# Project_Node_Sensors.net
KiCad netlist of a schematic drawn in Altium Designer
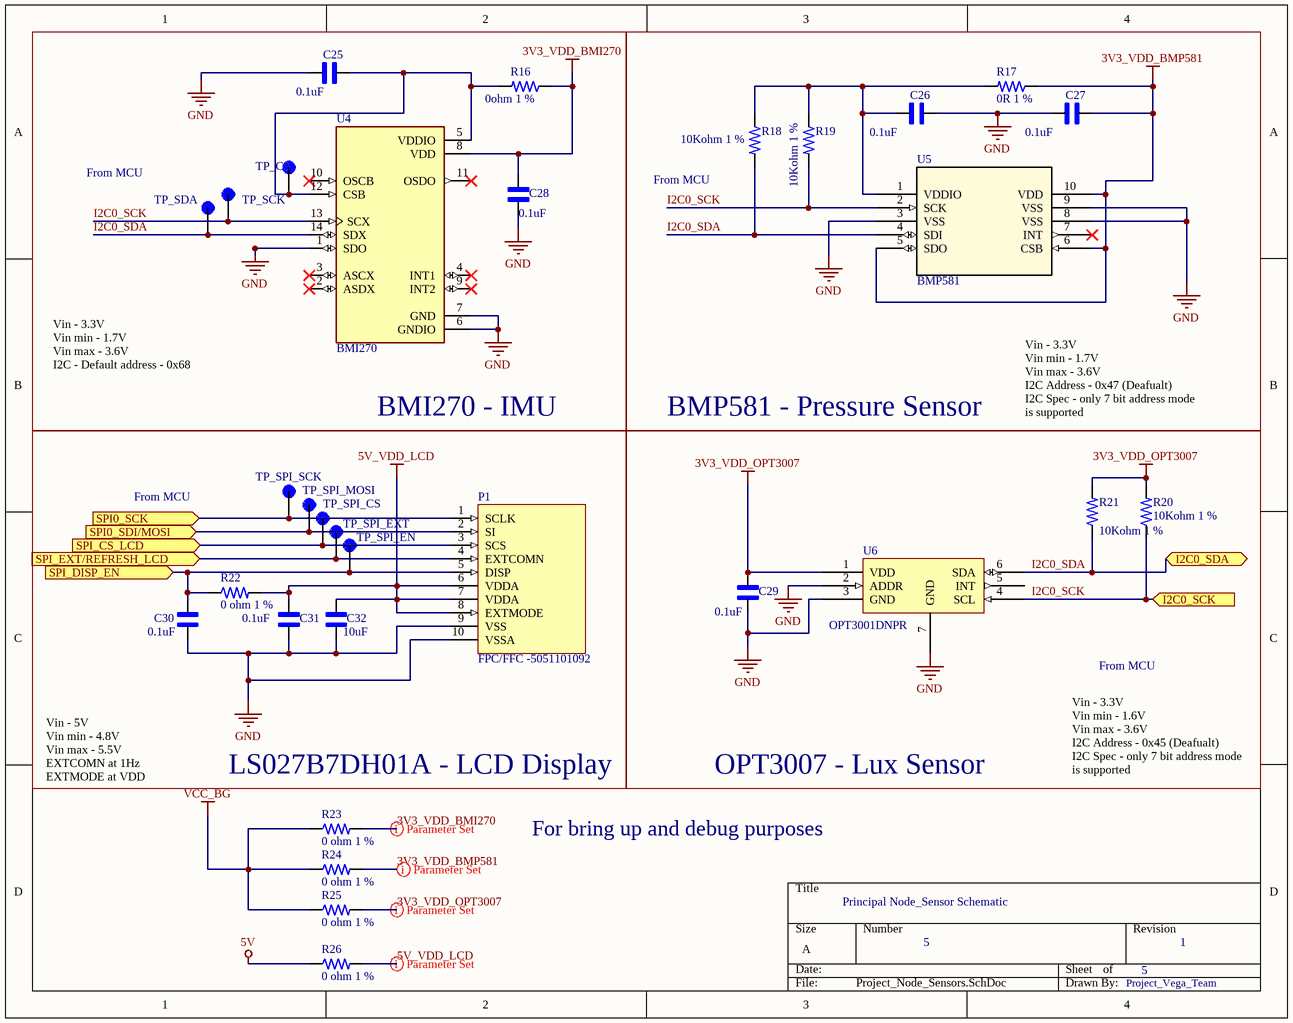
[diagram p0: Project_Node_Sensors.SchDoc]

(export (version "E")
  (design (tool "Eeschema 10.0.6"))
  (components
    (comp (ref "C25")
      (value "0.1uF")
      (footprint "CAPC1608X90")
      (description "0.1 ÂµF Â±10% 50V Ceramic Capacitor X7R 0603 (1608 Metric)")
      (fields (field (name "MF") "Yageo") (field (name "MP") "CC0603KRX7R9BB104"))
      (libsource (lib "Project_Vega") (part "CC0603KRX7R9BB104"))
    )
    (comp (ref "C26")
      (value "0.1uF")
      (footprint "CAPC1608X90")
      (description "0.1 ÂµF Â±10% 50V Ceramic Capacitor X7R 0603 (1608 Metric)")
      (fields (field (name "MF") "Yageo") (field (name "MP") "CC0603KRX7R9BB104"))
      (libsource (lib "Project_Vega") (part "CC0603KRX7R9BB104"))
    )
    (comp (ref "C27")
      (value "0.1uF")
      (footprint "CAPC1608X90")
      (description "0.1 ÂµF Â±10% 50V Ceramic Capacitor X7R 0603 (1608 Metric)")
      (fields (field (name "MF") "Yageo") (field (name "MP") "CC0603KRX7R9BB104"))
      (libsource (lib "Project_Vega") (part "CC0603KRX7R9BB104"))
    )
    (comp (ref "C28")
      (value "0.1uF")
      (footprint "CAPC1608X90")
      (description "0.1 ÂµF Â±10% 50V Ceramic Capacitor X7R 0603 (1608 Metric)")
      (fields (field (name "MF") "Yageo") (field (name "MP") "CC0603KRX7R9BB104"))
      (libsource (lib "") (part "CC0603KRX7R9BB104_2"))
    )
    (comp (ref "C29")
      (value "0.1uF")
      (footprint "CAPC1608X90")
      (description "0.1 ÂµF Â±10% 50V Ceramic Capacitor X7R 0603 (1608 Metric)")
      (fields (field (name "MF") "Yageo") (field (name "MP") "CC0603KRX7R9BB104"))
      (libsource (lib "") (part "CC0603KRX7R9BB104_1"))
    )
    (comp (ref "C30")
      (value "0.1uF")
      (footprint "CAPC1608X90")
      (description "0.1 ÂµF Â±10% 50V Ceramic Capacitor X7R 0603 (1608 Metric)")
      (fields (field (name "MF") "Yageo") (field (name "MP") "CC0603KRX7R9BB104"))
      (libsource (lib "") (part "CC0603KRX7R9BB104_1"))
    )
    (comp (ref "C31")
      (value "0.1uF")
      (footprint "CAPC1608X90")
      (description "0.1 ÂµF Â±10% 50V Ceramic Capacitor X7R 0603 (1608 Metric)")
      (fields (field (name "MF") "Yageo") (field (name "MP") "CC0603KRX7R9BB104"))
      (libsource (lib "") (part "CC0603KRX7R9BB104_1"))
    )
    (comp (ref "C32")
      (value "10uF")
      (footprint "CAPC1608X90")
      (description "0.1 ÂµF Â±10% 50V Ceramic Capacitor X7R 0603 (1608 Metric)")
      (fields (field (name "MF") "Yageo") (field (name "MP") "CC0603KRX7R9BB104"))
      (libsource (lib "") (part "CC0603KRX7R9BB104_1"))
    )
    (comp (ref "P1")
      (value "FPC/FFC -5051101092")
      (footprint "CON_5051101092_MOL")
      (fields (field (name "MANUFACTURER") "Molex") (field (name "MANUFACTURER PART NUMBER") "505110-1092"))
      (libsource (lib "Project_Vega") (part "5051101092"))
    )
    (comp (ref "R16")
      (value "0ohm 1 %")
      (footprint "RES_0603_1608X06")
      (description "SMD Chip Resistor, 140 Ohm, ± 1%, 100 mW, 0603 [1608 Metric], Thick Film, General Purpose")
      (fields
        (field (name "MANUFACTURER") "Yageo")
        (field (name "MANUFACTURER PART NUMBER") "RC0603FR-07140RL")
      )
      (libsource (lib "Project_Vega") (part "RC0603FR-07140RL"))
    )
    (comp (ref "R17")
      (value "0R 1 %")
      (footprint "RES_0603_1608X06")
      (description "SMD Chip Resistor, 140 Ohm, ± 1%, 100 mW, 0603 [1608 Metric], Thick Film, General Purpose")
      (fields
        (field (name "MANUFACTURER") "Yageo")
        (field (name "MANUFACTURER PART NUMBER") "RC0603FR-07140RL")
      )
      (libsource (lib "Project_Vega") (part "RC0603FR-07140RL"))
    )
    (comp (ref "R18")
      (value "10Kohm 1 %")
      (footprint "RES_0603_1608X06")
      (description "SMD Chip Resistor, 140 Ohm, ± 1%, 100 mW, 0603 [1608 Metric], Thick Film, General Purpose")
      (fields
        (field (name "MANUFACTURER") "Yageo")
        (field (name "MANUFACTURER PART NUMBER") "RC0603FR-07140RL")
      )
      (libsource (lib "Project_Vega") (part "RC0603FR-07140RL"))
    )
    (comp (ref "R19")
      (value "10Kohm 1 %")
      (footprint "RES_0603_1608X06")
      (description "SMD Chip Resistor, 140 Ohm, ± 1%, 100 mW, 0603 [1608 Metric], Thick Film, General Purpose")
      (fields
        (field (name "MANUFACTURER") "Yageo")
        (field (name "MANUFACTURER PART NUMBER") "RC0603FR-07140RL")
      )
      (libsource (lib "Project_Vega") (part "RC0603FR-07140RL"))
    )
    (comp (ref "R20")
      (value "10Kohm 1 %")
      (footprint "RES_0603_1608X06")
      (description "SMD Chip Resistor, 140 Ohm, ± 1%, 100 mW, 0603 [1608 Metric], Thick Film, General Purpose")
      (fields
        (field (name "MANUFACTURER") "Yageo")
        (field (name "MANUFACTURER PART NUMBER") "RC0603FR-07140RL")
      )
      (libsource (lib "Project_Vega") (part "RC0603FR-07140RL"))
    )
    (comp (ref "R21")
      (value "10Kohm 1 %")
      (footprint "RES_0603_1608X06")
      (description "SMD Chip Resistor, 140 Ohm, ± 1%, 100 mW, 0603 [1608 Metric], Thick Film, General Purpose")
      (fields
        (field (name "MANUFACTURER") "Yageo")
        (field (name "MANUFACTURER PART NUMBER") "RC0603FR-07140RL")
      )
      (libsource (lib "Project_Vega") (part "RC0603FR-07140RL"))
    )
    (comp (ref "R22")
      (value "0 ohm 1 %")
      (footprint "RES_0603_1608X06")
      (description "SMD Chip Resistor, 140 Ohm, ± 1%, 100 mW, 0603 [1608 Metric], Thick Film, General Purpose")
      (fields
        (field (name "MANUFACTURER") "Yageo")
        (field (name "MANUFACTURER PART NUMBER") "RC0603FR-07140RL")
      )
      (libsource (lib "Project_Vega") (part "RC0603FR-07140RL"))
    )
    (comp (ref "R23")
      (value "0 ohm 1 %")
      (footprint "RES_0603_1608X06")
      (description "SMD Chip Resistor, 140 Ohm, ± 1%, 100 mW, 0603 [1608 Metric], Thick Film, General Purpose")
      (fields
        (field (name "MANUFACTURER") "Yageo")
        (field (name "MANUFACTURER PART NUMBER") "RC0603FR-07140RL")
      )
      (libsource (lib "Project_Vega") (part "RC0603FR-07140RL"))
    )
    (comp (ref "R24")
      (value "0 ohm 1 %")
      (footprint "RES_0603_1608X06")
      (description "SMD Chip Resistor, 140 Ohm, ± 1%, 100 mW, 0603 [1608 Metric], Thick Film, General Purpose")
      (fields
        (field (name "MANUFACTURER") "Yageo")
        (field (name "MANUFACTURER PART NUMBER") "RC0603FR-07140RL")
      )
      (libsource (lib "Project_Vega") (part "RC0603FR-07140RL"))
    )
    (comp (ref "R25")
      (value "0 ohm 1 %")
      (footprint "RES_0603_1608X06")
      (description "SMD Chip Resistor, 140 Ohm, ± 1%, 100 mW, 0603 [1608 Metric], Thick Film, General Purpose")
      (fields
        (field (name "MANUFACTURER") "Yageo")
        (field (name "MANUFACTURER PART NUMBER") "RC0603FR-07140RL")
      )
      (libsource (lib "Project_Vega") (part "RC0603FR-07140RL"))
    )
    (comp (ref "R26")
      (value "0 ohm 1 %")
      (footprint "RES_0603_1608X06")
      (description "SMD Chip Resistor, 140 Ohm, ± 1%, 100 mW, 0603 [1608 Metric], Thick Film, General Purpose")
      (fields
        (field (name "MANUFACTURER") "Yageo")
        (field (name "MANUFACTURER PART NUMBER") "RC0603FR-07140RL")
      )
      (libsource (lib "Project_Vega") (part "RC0603FR-07140RL"))
    )
    (comp (ref "TP_CS")
      (value "Test_point")
      (footprint "1")
      (description "SMT Test Point- Mininature-1000 pc Reels")
      (fields (field (name "MP") "5019") (field (name "MF") "Keystone Electronics"))
      (libsource (lib "Project_Vega") (part "Test_point"))
    )
    (comp (ref "TP_SCK")
      (value "Test_point")
      (footprint "1")
      (description "SMT Test Point- Mininature-1000 pc Reels")
      (fields (field (name "MP") "5019") (field (name "MF") "Keystone Electronics"))
      (libsource (lib "Project_Vega") (part "Test_point"))
    )
    (comp (ref "TP_SDA")
      (value "Test_point")
      (footprint "1")
      (description "SMT Test Point- Mininature-1000 pc Reels")
      (fields (field (name "MP") "5019") (field (name "MF") "Keystone Electronics"))
      (libsource (lib "Project_Vega") (part "Test_point"))
    )
    (comp (ref "TP_SPI_CS")
      (value "Test_point")
      (footprint "1")
      (description "SMT Test Point- Mininature-1000 pc Reels")
      (fields (field (name "MP") "5019") (field (name "MF") "Keystone Electronics"))
      (libsource (lib "Project_Vega") (part "Test_point"))
    )
    (comp (ref "TP_SPI_EN")
      (value "Test_point")
      (footprint "1")
      (description "SMT Test Point- Mininature-1000 pc Reels")
      (fields (field (name "MP") "5019") (field (name "MF") "Keystone Electronics"))
      (libsource (lib "Project_Vega") (part "Test_point"))
    )
    (comp (ref "TP_SPI_EXT")
      (value "Test_point")
      (footprint "1")
      (description "SMT Test Point- Mininature-1000 pc Reels")
      (fields (field (name "MP") "5019") (field (name "MF") "Keystone Electronics"))
      (libsource (lib "Project_Vega") (part "Test_point"))
    )
    (comp (ref "TP_SPI_MOSI")
      (value "Test_point")
      (footprint "1")
      (description "SMT Test Point- Mininature-1000 pc Reels")
      (fields (field (name "MP") "5019") (field (name "MF") "Keystone Electronics"))
      (libsource (lib "Project_Vega") (part "Test_point"))
    )
    (comp (ref "TP_SPI_SCK")
      (value "Test_point")
      (footprint "1")
      (description "SMT Test Point- Mininature-1000 pc Reels")
      (fields (field (name "MP") "5019") (field (name "MF") "Keystone Electronics"))
      (libsource (lib "Project_Vega") (part "Test_point"))
    )
    (comp (ref "U4")
      (value "BMI270")
      (footprint "XDCR_BMI270")
      (description "Accelerometer, Gyroscope, 6 Axis Sensor IÂ²C, SPI Output")
      (fields (field (name "DIGI-KEY_PART_NUMBER") "828-1091-2-ND") (field (name "MF") "Bosch Sensortec"))
      (libsource (lib "Project_Vega") (part "BMI270"))
    )
    (comp (ref "U5")
      (value "BMP581")
      (footprint "QFN10_BMP581_BOS-M")
      (description "No Description Available")
      (libsource (lib "Project_Vega") (part "BMP581"))
    )
    (comp (ref "U6")
      (value "OPT3001DNPR")
      (footprint "OPT3001-SON127P600-8N")
      (description "Digital ambient light sensor (ALS) with high-precision human-eye response 6-USON -40 to 85")
      (fields (field (name "MANUFACTURER") "Texas Instruments"))
      (libsource (lib "Project_Vega") (part "OPT3001DNPR"))
    )
  )
  (nets
    (net (code "1") (name "/I2C0_SCK") (class "Default")
      (node (ref "R19") (pin "2") (pinfunction "2_2") (pintype "passive"))
      (node (ref "R20") (pin "1") (pinfunction "1_1") (pintype "passive"))
      (node (ref "TP_SCK") (pin "TP") (pinfunction "I2C_SCK_TP") (pintype "passive"))
      (node (ref "U4") (pin "13") (pinfunction "SCX_13") (pintype "input"))
      (node (ref "U5") (pin "2") (pinfunction "SCK_2") (pintype "input"))
      (node (ref "U6") (pin "4") (pinfunction "SCL_4") (pintype "input"))
    )
    (net (code "2") (name "/I2C0_SDA") (class "Default")
      (node (ref "R18") (pin "2") (pinfunction "2_2") (pintype "passive"))
      (node (ref "R21") (pin "1") (pinfunction "1_1") (pintype "passive"))
      (node (ref "TP_SDA") (pin "TP") (pinfunction "I2C_SCK_TP") (pintype "passive"))
      (node (ref "U4") (pin "14") (pinfunction "SDX_14") (pintype "bidirectional"))
      (node (ref "U5") (pin "4") (pinfunction "SDI_4") (pintype "bidirectional"))
      (node (ref "U6") (pin "6") (pinfunction "SDA_6") (pintype "bidirectional"))
    )
    (net (code "3") (name "/SPI0_SCK") (class "Default")
      (node (ref "P1") (pin "1") (pinfunction "SCLK_1") (pintype "input"))
      (node (ref "TP_SPI_SCK") (pin "TP") (pinfunction "I2C_SCK_TP") (pintype "passive"))
    )
    (net (code "4") (name "/SPI0_SDI{slash}MOSI") (class "Default")
      (node (ref "P1") (pin "2") (pinfunction "SI_2") (pintype "input"))
      (node (ref "TP_SPI_MOSI") (pin "TP") (pinfunction "I2C_SCK_TP") (pintype "passive"))
    )
    (net (code "5") (name "/SPI_CS_LCD") (class "Default")
      (node (ref "P1") (pin "3") (pinfunction "SCS_3") (pintype "input"))
      (node (ref "TP_SPI_CS") (pin "TP") (pinfunction "I2C_SCK_TP") (pintype "passive"))
    )
    (net (code "6") (name "/SPI_DISP_EN") (class "Default")
      (node (ref "C30") (pin "2") (pinfunction "2_2") (pintype "passive"))
      (node (ref "P1") (pin "5") (pinfunction "DISP_5") (pintype "input"))
      (node (ref "R22") (pin "1") (pinfunction "1_1") (pintype "passive"))
      (node (ref "TP_SPI_EN") (pin "TP") (pinfunction "I2C_SCK_TP") (pintype "passive"))
    )
    (net (code "7") (name "/SPI_EXT{slash}REFRESH_LCD") (class "Default")
      (node (ref "P1") (pin "4") (pinfunction "EXTCOMN_4") (pintype "input"))
      (node (ref "TP_SPI_EXT") (pin "TP") (pinfunction "I2C_SCK_TP") (pintype "passive"))
    )
    (net (code "8") (name "3V3_VDD_BMI270") (class "Default")
      (node (ref "C28") (pin "1") (pinfunction "1_1") (pintype "passive"))
      (node (ref "R16") (pin "1") (pinfunction "1_1") (pintype "passive"))
      (node (ref "R23") (pin "2") (pinfunction "2_2") (pintype "passive"))
      (node (ref "U4") (pin "8") (pinfunction "VDD_8") (pintype "power_in"))
    )
    (net (code "9") (name "3V3_VDD_BMP581") (class "Default")
      (node (ref "C27") (pin "2") (pinfunction "2_2") (pintype "passive"))
      (node (ref "R17") (pin "1") (pinfunction "1_1") (pintype "passive"))
      (node (ref "R24") (pin "2") (pinfunction "2_2") (pintype "passive"))
      (node (ref "U5") (pin "10") (pinfunction "VDD_10") (pintype "power_in"))
      (node (ref "U5") (pin "5") (pinfunction "SDO_5") (pintype "bidirectional"))
      (node (ref "U5") (pin "6") (pinfunction "CSB_6") (pintype "input"))
    )
    (net (code "10") (name "3V3_VDD_OPT3007") (class "Default")
      (node (ref "C29") (pin "2") (pinfunction "2_2") (pintype "passive"))
      (node (ref "R20") (pin "2") (pinfunction "2_2") (pintype "passive"))
      (node (ref "R21") (pin "2") (pinfunction "2_2") (pintype "passive"))
      (node (ref "R25") (pin "2") (pinfunction "2_2") (pintype "passive"))
      (node (ref "U6") (pin "1") (pinfunction "VDD_1") (pintype "power_in"))
    )
    (net (code "11") (name "5V") (class "Default")
      (node (ref "R26") (pin "1") (pinfunction "1_1") (pintype "passive"))
    )
    (net (code "12") (name "5V_VDD_LCD") (class "Default")
      (node (ref "C31") (pin "2") (pinfunction "2_2") (pintype "passive"))
      (node (ref "C32") (pin "2") (pinfunction "2_2") (pintype "passive"))
      (node (ref "P1") (pin "6") (pinfunction "VDDA_6") (pintype "power_in"))
      (node (ref "P1") (pin "7") (pinfunction "VDDA_7") (pintype "power_in"))
      (node (ref "P1") (pin "8") (pinfunction "EXTMODE_8") (pintype "input"))
      (node (ref "R22") (pin "2") (pinfunction "2_2") (pintype "passive"))
      (node (ref "R26") (pin "2") (pinfunction "2_2") (pintype "passive"))
    )
    (net (code "13") (name "GND") (class "Default")
      (node (ref "C25") (pin "1") (pinfunction "1_1") (pintype "passive"))
      (node (ref "C26") (pin "2") (pinfunction "2_2") (pintype "passive"))
      (node (ref "C27") (pin "1") (pinfunction "1_1") (pintype "passive"))
      (node (ref "C28") (pin "2") (pinfunction "2_2") (pintype "passive"))
      (node (ref "C29") (pin "1") (pinfunction "1_1") (pintype "passive"))
      (node (ref "C30") (pin "1") (pinfunction "1_1") (pintype "passive"))
      (node (ref "C31") (pin "1") (pinfunction "1_1") (pintype "passive"))
      (node (ref "C32") (pin "1") (pinfunction "1_1") (pintype "passive"))
      (node (ref "P1") (pin "10") (pinfunction "VSSA_10") (pintype "power_in"))
      (node (ref "P1") (pin "9") (pinfunction "VSS_9") (pintype "power_in"))
      (node (ref "U4") (pin "1") (pinfunction "SDO_1") (pintype "bidirectional"))
      (node (ref "U4") (pin "6") (pinfunction "GNDIO_6") (pintype "power_in"))
      (node (ref "U4") (pin "7") (pinfunction "GND_7") (pintype "power_in"))
      (node (ref "U5") (pin "3") (pinfunction "VSS_3") (pintype "power_in"))
      (node (ref "U5") (pin "8") (pinfunction "VSS_8") (pintype "power_in"))
      (node (ref "U5") (pin "9") (pinfunction "VSS_9") (pintype "power_in"))
      (node (ref "U6") (pin "2") (pinfunction "ADDR_2") (pintype "input"))
      (node (ref "U6") (pin "3") (pinfunction "GND_3") (pintype "power_in"))
      (node (ref "U6") (pin "7") (pinfunction "GND_7") (pintype "passive"))
    )
    (net (code "14") (name "Net-(TP_CS-I2C_SCK)") (class "Default")
      (node (ref "C25") (pin "2") (pinfunction "2_2") (pintype "passive"))
      (node (ref "R16") (pin "2") (pinfunction "2_2") (pintype "passive"))
      (node (ref "TP_CS") (pin "TP") (pinfunction "I2C_SCK_TP") (pintype "passive"))
      (node (ref "U4") (pin "12") (pinfunction "CSB_12") (pintype "input"))
      (node (ref "U4") (pin "5") (pinfunction "VDDIO_5") (pintype "power_in"))
    )
    (net (code "15") (name "Net-(U5-VDDIO)") (class "Default")
      (node (ref "C26") (pin "1") (pinfunction "1_1") (pintype "passive"))
      (node (ref "R17") (pin "2") (pinfunction "2_2") (pintype "passive"))
      (node (ref "R18") (pin "1") (pinfunction "1_1") (pintype "passive"))
      (node (ref "R19") (pin "1") (pinfunction "1_1") (pintype "passive"))
      (node (ref "U5") (pin "1") (pinfunction "VDDIO_1") (pintype "power_in"))
    )
    (net (code "16") (name "VCC_BG") (class "Default")
      (node (ref "R23") (pin "1") (pinfunction "1_1") (pintype "passive"))
      (node (ref "R24") (pin "1") (pinfunction "1_1") (pintype "passive"))
      (node (ref "R25") (pin "1") (pinfunction "1_1") (pintype "passive"))
    )
    (net (code "17") (name "unconnected-(U4-ASCX-Pad3)") (class "Default")
      (node (ref "U4") (pin "3") (pinfunction "ASCX_3") (pintype "bidirectional+no_connect"))
    )
    (net (code "18") (name "unconnected-(U4-ASDX-Pad2)") (class "Default")
      (node (ref "U4") (pin "2") (pinfunction "ASDX_2") (pintype "bidirectional+no_connect"))
    )
    (net (code "19") (name "unconnected-(U4-INT1-Pad4)") (class "Default")
      (node (ref "U4") (pin "4") (pinfunction "INT1_4") (pintype "bidirectional+no_connect"))
    )
    (net (code "20") (name "unconnected-(U4-INT2-Pad9)") (class "Default")
      (node (ref "U4") (pin "9") (pinfunction "INT2_9") (pintype "bidirectional+no_connect"))
    )
    (net (code "21") (name "unconnected-(U4-OSCB-Pad10)") (class "Default")
      (node (ref "U4") (pin "10") (pinfunction "OSCB_10") (pintype "input+no_connect"))
    )
    (net (code "22") (name "unconnected-(U4-OSDO-Pad11)") (class "Default")
      (node (ref "U4") (pin "11") (pinfunction "OSDO_11") (pintype "output+no_connect"))
    )
    (net (code "23") (name "unconnected-(U5-INT-Pad7)") (class "Default")
      (node (ref "U5") (pin "7") (pinfunction "INT_7") (pintype "output+no_connect"))
    )
    (net (code "24") (name "unconnected-(U6-INT-Pad5)") (class "Default")
      (node (ref "U6") (pin "5") (pinfunction "INT_5") (pintype "output"))
    )
  )
)
